# radio_module_V3_0.net
KiCad netlist of a schematic drawn in EAGLE
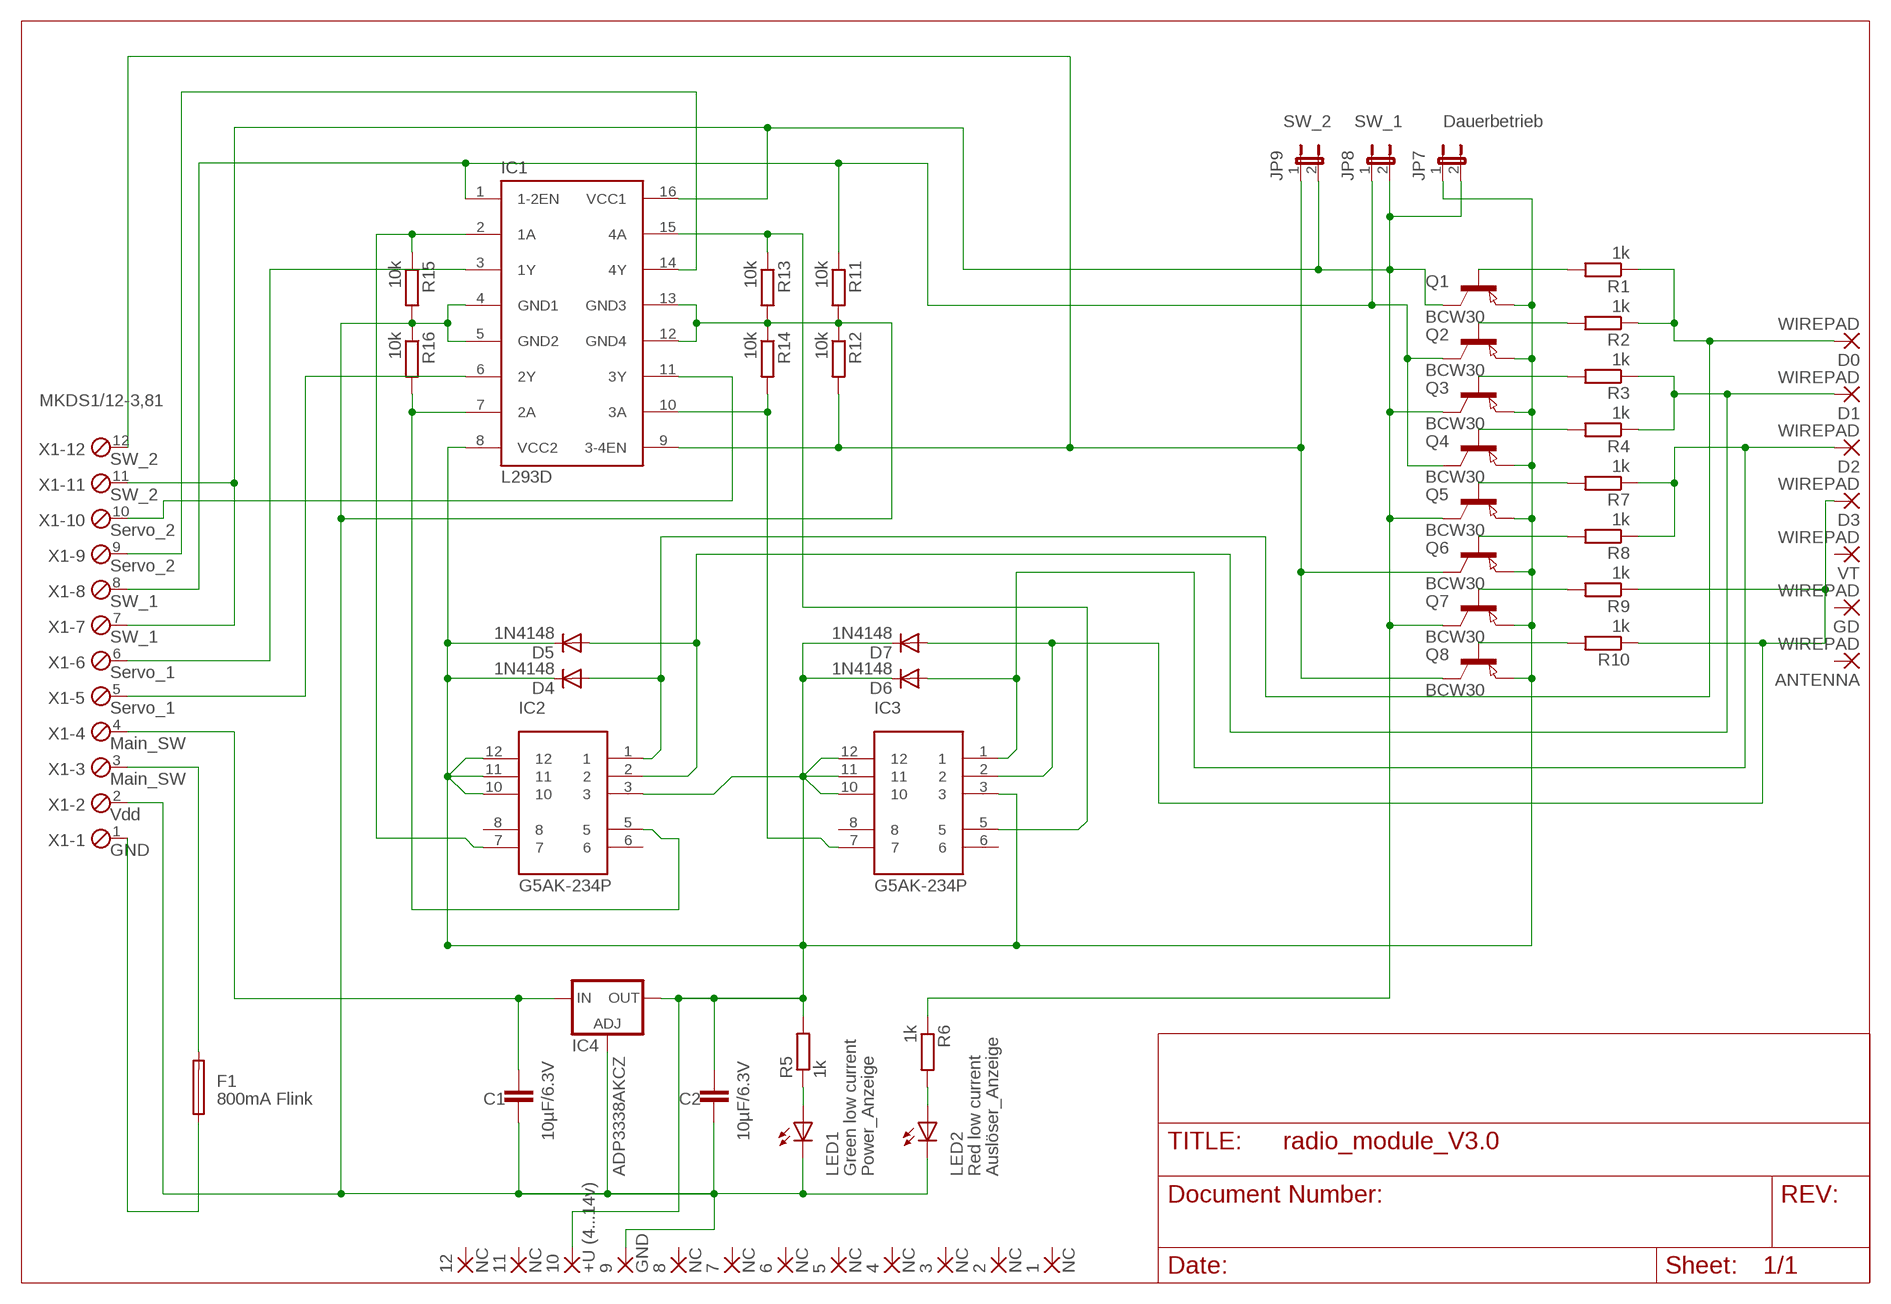
[diagram p0: schematic, sheet 1]

(export (version "E")
  (design (tool "Eeschema 10.0.6"))
  (components
    (comp (ref "1")
      (value "NC")
      (footprint "eagle-import:1,6_0,9")
      (libsource (lib "eagle-import") (part "1,6/0,9"))
    )
    (comp (ref "2")
      (value "NC")
      (footprint "eagle-import:1,6_0,9")
      (libsource (lib "eagle-import") (part "1,6/0,9"))
    )
    (comp (ref "3")
      (value "NC")
      (footprint "eagle-import:1,6_0,9")
      (libsource (lib "eagle-import") (part "1,6/0,9"))
    )
    (comp (ref "4")
      (value "NC")
      (footprint "eagle-import:1,6_0,9")
      (libsource (lib "eagle-import") (part "1,6/0,9"))
    )
    (comp (ref "5")
      (value "NC")
      (footprint "eagle-import:1,6_0,9")
      (libsource (lib "eagle-import") (part "1,6/0,9"))
    )
    (comp (ref "6")
      (value "NC")
      (footprint "eagle-import:1,6_0,9")
      (libsource (lib "eagle-import") (part "1,6/0,9"))
    )
    (comp (ref "7")
      (value "NC")
      (footprint "eagle-import:1,6_0,9")
      (libsource (lib "eagle-import") (part "1,6/0,9"))
    )
    (comp (ref "8")
      (value "NC")
      (footprint "eagle-import:1,6_0,9")
      (libsource (lib "eagle-import") (part "1,6/0,9"))
    )
    (comp (ref "9")
      (value "GND")
      (footprint "eagle-import:1,6_0,9")
      (libsource (lib "eagle-import") (part "1,6/0,9"))
    )
    (comp (ref "10")
      (value "+U (4...14v)")
      (footprint "eagle-import:1,6_0,9")
      (libsource (lib "eagle-import") (part "1,6/0,9"))
    )
    (comp (ref "11")
      (value "NC")
      (footprint "eagle-import:1,6_0,9")
      (libsource (lib "eagle-import") (part "1,6/0,9"))
    )
    (comp (ref "12")
      (value "NC")
      (footprint "eagle-import:1,6_0,9")
      (libsource (lib "eagle-import") (part "1,6/0,9"))
    )
    (comp (ref "ANTENNA")
      (value "WIREPAD")
      (footprint "eagle-import:1,6_0,9")
      (libsource (lib "eagle-import") (part "1,6/0,9"))
    )
    (comp (ref "C1")
      (value "10µF/6.3V")
      (footprint "eagle-import:C0805")
      (libsource (lib "eagle-import") (part "C-EUC0805"))
    )
    (comp (ref "C2")
      (value "10µF/6.3V")
      (footprint "eagle-import:C0805")
      (libsource (lib "eagle-import") (part "C-EUC0805"))
    )
    (comp (ref "D0")
      (value "WIREPAD")
      (footprint "eagle-import:1,6_0,9")
      (libsource (lib "eagle-import") (part "1,6/0,9"))
    )
    (comp (ref "D1")
      (value "WIREPAD")
      (footprint "eagle-import:1,6_0,9")
      (libsource (lib "eagle-import") (part "1,6/0,9"))
    )
    (comp (ref "D2")
      (value "WIREPAD")
      (footprint "eagle-import:1,6_0,9")
      (libsource (lib "eagle-import") (part "1,6/0,9"))
    )
    (comp (ref "D3")
      (value "WIREPAD")
      (footprint "eagle-import:1,6_0,9")
      (libsource (lib "eagle-import") (part "1,6/0,9"))
    )
    (comp (ref "D4")
      (value "1N4148")
      (footprint "eagle-import:DO35-7")
      (libsource (lib "eagle-import") (part "1N4148DO35-7"))
    )
    (comp (ref "D5")
      (value "1N4148")
      (footprint "eagle-import:DO35-7")
      (libsource (lib "eagle-import") (part "1N4148DO35-7"))
    )
    (comp (ref "D6")
      (value "1N4148")
      (footprint "eagle-import:DO35-7")
      (libsource (lib "eagle-import") (part "1N4148DO35-7"))
    )
    (comp (ref "D7")
      (value "1N4148")
      (footprint "eagle-import:DO35-7")
      (libsource (lib "eagle-import") (part "1N4148DO35-7"))
    )
    (comp (ref "F1")
      (value "800mA Flink")
      (footprint "eagle-import:19560")
      (libsource (lib "eagle-import") (part "FUSE19560"))
    )
    (comp (ref "GD")
      (value "WIREPAD")
      (footprint "eagle-import:1,6_0,9")
      (libsource (lib "eagle-import") (part "1,6/0,9"))
    )
    (comp (ref "IC1")
      (value "L293D")
      (footprint "eagle-import:DIL16")
      (libsource (lib "eagle-import") (part "L293D"))
    )
    (comp (ref "IC2")
      (value "G5AK-234P")
      (footprint "eagle-import:G5AK-234P")
      (libsource (lib "eagle-import") (part "G5AK-234P"))
    )
    (comp (ref "IC3")
      (value "G5AK-234P")
      (footprint "eagle-import:G5AK-234P")
      (libsource (lib "eagle-import") (part "G5AK-234P"))
    )
    (comp (ref "IC4")
      (value "ADP3338AKCZ")
      (footprint "eagle-import:SOT223")
      (libsource (lib "eagle-import") (part "LD117A?S12TR"))
    )
    (comp (ref "JP7")
      (value "Dauerbetrieb")
      (footprint "eagle-import:JP1")
      (libsource (lib "eagle-import") (part "JP1E"))
    )
    (comp (ref "JP8")
      (value "SW_1")
      (footprint "eagle-import:JP1")
      (libsource (lib "eagle-import") (part "JP1E"))
    )
    (comp (ref "JP9")
      (value "SW_2")
      (footprint "eagle-import:JP1")
      (libsource (lib "eagle-import") (part "JP1E"))
    )
    (comp (ref "LED1")
      (value "Green low current")
      (footprint "eagle-import:LED3MM")
      (libsource (lib "eagle-import") (part "LED3MM"))
    )
    (comp (ref "LED2")
      (value "Red low current")
      (footprint "eagle-import:LED3MM")
      (libsource (lib "eagle-import") (part "LED3MM"))
    )
    (comp (ref "Q1")
      (value "BCW30")
      (footprint "eagle-import:SOT23")
      (libsource (lib "eagle-import") (part "PNP-TRANSISTOR_SOT23"))
    )
    (comp (ref "Q2")
      (value "BCW30")
      (footprint "eagle-import:SOT23")
      (libsource (lib "eagle-import") (part "PNP-TRANSISTOR_SOT23"))
    )
    (comp (ref "Q3")
      (value "BCW30")
      (footprint "eagle-import:SOT23")
      (libsource (lib "eagle-import") (part "PNP-TRANSISTOR_SOT23"))
    )
    (comp (ref "Q4")
      (value "BCW30")
      (footprint "eagle-import:SOT23")
      (libsource (lib "eagle-import") (part "PNP-TRANSISTOR_SOT23"))
    )
    (comp (ref "Q5")
      (value "BCW30")
      (footprint "eagle-import:SOT23")
      (libsource (lib "eagle-import") (part "PNP-TRANSISTOR_SOT23"))
    )
    (comp (ref "Q6")
      (value "BCW30")
      (footprint "eagle-import:SOT23")
      (libsource (lib "eagle-import") (part "PNP-TRANSISTOR_SOT23"))
    )
    (comp (ref "Q7")
      (value "BCW30")
      (footprint "eagle-import:SOT23")
      (libsource (lib "eagle-import") (part "PNP-TRANSISTOR_SOT23"))
    )
    (comp (ref "Q8")
      (value "BCW30")
      (footprint "eagle-import:SOT23")
      (libsource (lib "eagle-import") (part "PNP-TRANSISTOR_SOT23"))
    )
    (comp (ref "R1")
      (value "1k")
      (footprint "eagle-import:R0402")
      (libsource (lib "eagle-import") (part "R-EU_R0402"))
    )
    (comp (ref "R2")
      (value "1k")
      (footprint "eagle-import:R0402")
      (libsource (lib "eagle-import") (part "R-EU_R0402"))
    )
    (comp (ref "R3")
      (value "1k")
      (footprint "eagle-import:R0402")
      (libsource (lib "eagle-import") (part "R-EU_R0402"))
    )
    (comp (ref "R4")
      (value "1k")
      (footprint "eagle-import:R0402")
      (libsource (lib "eagle-import") (part "R-EU_R0402"))
    )
    (comp (ref "R5")
      (value "1k")
      (footprint "eagle-import:R0402")
      (libsource (lib "eagle-import") (part "R-EU_R0402"))
    )
    (comp (ref "R6")
      (value "1k")
      (footprint "eagle-import:R0402")
      (libsource (lib "eagle-import") (part "R-EU_R0402"))
    )
    (comp (ref "R7")
      (value "1k")
      (footprint "eagle-import:R0402")
      (libsource (lib "eagle-import") (part "R-EU_R0402"))
    )
    (comp (ref "R8")
      (value "1k")
      (footprint "eagle-import:R0402")
      (libsource (lib "eagle-import") (part "R-EU_R0402"))
    )
    (comp (ref "R9")
      (value "1k")
      (footprint "eagle-import:R0402")
      (libsource (lib "eagle-import") (part "R-EU_R0402"))
    )
    (comp (ref "R10")
      (value "1k")
      (footprint "eagle-import:R0402")
      (libsource (lib "eagle-import") (part "R-EU_R0402"))
    )
    (comp (ref "R11")
      (value "10k")
      (footprint "eagle-import:R0402")
      (libsource (lib "eagle-import") (part "R-EU_R0402"))
    )
    (comp (ref "R12")
      (value "10k")
      (footprint "eagle-import:R0402")
      (libsource (lib "eagle-import") (part "R-EU_R0402"))
    )
    (comp (ref "R13")
      (value "10k")
      (footprint "eagle-import:R0402")
      (libsource (lib "eagle-import") (part "R-EU_R0402"))
    )
    (comp (ref "R14")
      (value "10k")
      (footprint "eagle-import:R0402")
      (libsource (lib "eagle-import") (part "R-EU_R0402"))
    )
    (comp (ref "R15")
      (value "10k")
      (footprint "eagle-import:R0402")
      (libsource (lib "eagle-import") (part "R-EU_R0402"))
    )
    (comp (ref "R16")
      (value "10k")
      (footprint "eagle-import:R0402")
      (libsource (lib "eagle-import") (part "R-EU_R0402"))
    )
    (comp (ref "VT")
      (value "WIREPAD")
      (footprint "eagle-import:1,6_0,9")
      (libsource (lib "eagle-import") (part "1,6/0,9"))
    )
    (comp (ref "X1")
      (value "MKDS1/12-3,81")
      (footprint "eagle-import:12POL381")
      (libsource (lib "eagle-import") (part "MKDS1/12-3,81"))
    )
  )
  (nets
    (net (code "1") (name "Net-(9-P)") (class "Default")
      (node (ref "9") (pin "1") (pinfunction "P_1") (pintype "passive"))
      (node (ref "C1") (pin "2") (pinfunction "2_2") (pintype "passive"))
      (node (ref "C2") (pin "2") (pinfunction "2_2") (pintype "passive"))
      (node (ref "IC1") (pin "12") (pinfunction "GND4_12") (pintype "power_in"))
      (node (ref "IC1") (pin "13") (pinfunction "GND3_13") (pintype "power_in"))
      (node (ref "IC1") (pin "4") (pinfunction "GND1_4") (pintype "power_in"))
      (node (ref "IC1") (pin "5") (pinfunction "GND2_5") (pintype "power_in"))
      (node (ref "IC4") (pin "1") (pinfunction "ADJ_1") (pintype "input"))
      (node (ref "LED1") (pin "K") (pinfunction "C_K") (pintype "passive"))
      (node (ref "LED2") (pin "K") (pinfunction "C_K") (pintype "passive"))
      (node (ref "R11") (pin "2") (pinfunction "2_2") (pintype "passive"))
      (node (ref "R12") (pin "1") (pinfunction "1_1") (pintype "passive"))
      (node (ref "R13") (pin "2") (pinfunction "2_2") (pintype "passive"))
      (node (ref "R14") (pin "1") (pinfunction "1_1") (pintype "passive"))
      (node (ref "R15") (pin "2") (pinfunction "2_2") (pintype "passive"))
      (node (ref "R16") (pin "1") (pinfunction "1_1") (pintype "passive"))
      (node (ref "X1") (pin "2") (pinfunction "1_2") (pintype "passive"))
    )
    (net (code "2") (name "Net-(10-P)") (class "Default")
      (node (ref "10") (pin "1") (pinfunction "P_1") (pintype "passive"))
      (node (ref "C2") (pin "1") (pinfunction "1_1") (pintype "passive"))
      (node (ref "D4") (pin "C") (pinfunction "C_C") (pintype "passive"))
      (node (ref "D5") (pin "C") (pinfunction "C_C") (pintype "passive"))
      (node (ref "D6") (pin "C") (pinfunction "C_C") (pintype "passive"))
      (node (ref "D7") (pin "C") (pinfunction "C_C") (pintype "passive"))
      (node (ref "IC1") (pin "8") (pinfunction "VCC2_8") (pintype "power_in"))
      (node (ref "IC2") (pin "10") (pinfunction "10_10") (pintype "bidirectional"))
      (node (ref "IC2") (pin "11") (pinfunction "11_11") (pintype "bidirectional"))
      (node (ref "IC2") (pin "12") (pinfunction "12_12") (pintype "bidirectional"))
      (node (ref "IC2") (pin "3") (pinfunction "3_3") (pintype "bidirectional"))
      (node (ref "IC3") (pin "10") (pinfunction "10_10") (pintype "bidirectional"))
      (node (ref "IC3") (pin "11") (pinfunction "11_11") (pintype "bidirectional"))
      (node (ref "IC3") (pin "12") (pinfunction "12_12") (pintype "bidirectional"))
      (node (ref "IC3") (pin "3") (pinfunction "3_3") (pintype "bidirectional"))
      (node (ref "IC4") (pin "4") (pinfunction "OUT_4") (pintype "passive"))
      (node (ref "JP7") (pin "1") (pinfunction "1_1") (pintype "passive"))
      (node (ref "Q1") (pin "2") (pinfunction "E_2") (pintype "passive"))
      (node (ref "Q2") (pin "2") (pinfunction "E_2") (pintype "passive"))
      (node (ref "Q3") (pin "2") (pinfunction "E_2") (pintype "passive"))
      (node (ref "Q4") (pin "2") (pinfunction "E_2") (pintype "passive"))
      (node (ref "Q5") (pin "2") (pinfunction "E_2") (pintype "passive"))
      (node (ref "Q6") (pin "2") (pinfunction "E_2") (pintype "passive"))
      (node (ref "Q7") (pin "2") (pinfunction "E_2") (pintype "passive"))
      (node (ref "Q8") (pin "2") (pinfunction "E_2") (pintype "passive"))
      (node (ref "R5") (pin "2") (pinfunction "2_2") (pintype "passive"))
    )
    (net (code "3") (name "Net-(D0-P)") (class "Default")
      (node (ref "D0") (pin "1") (pinfunction "P_1") (pintype "passive"))
      (node (ref "D4") (pin "A") (pinfunction "A_A") (pintype "passive"))
      (node (ref "IC2") (pin "1") (pinfunction "1_1") (pintype "bidirectional"))
      (node (ref "R1") (pin "1") (pinfunction "1_1") (pintype "passive"))
      (node (ref "R2") (pin "1") (pinfunction "1_1") (pintype "passive"))
    )
    (net (code "4") (name "Net-(D1-P)") (class "Default")
      (node (ref "D1") (pin "1") (pinfunction "P_1") (pintype "passive"))
      (node (ref "D5") (pin "A") (pinfunction "A_A") (pintype "passive"))
      (node (ref "IC2") (pin "2") (pinfunction "2_2") (pintype "bidirectional"))
      (node (ref "R3") (pin "1") (pinfunction "1_1") (pintype "passive"))
      (node (ref "R4") (pin "1") (pinfunction "1_1") (pintype "passive"))
    )
    (net (code "5") (name "Net-(D2-P)") (class "Default")
      (node (ref "D2") (pin "1") (pinfunction "P_1") (pintype "passive"))
      (node (ref "D6") (pin "A") (pinfunction "A_A") (pintype "passive"))
      (node (ref "IC3") (pin "1") (pinfunction "1_1") (pintype "bidirectional"))
      (node (ref "R7") (pin "1") (pinfunction "1_1") (pintype "passive"))
      (node (ref "R8") (pin "1") (pinfunction "1_1") (pintype "passive"))
    )
    (net (code "6") (name "Net-(D3-P)") (class "Default")
      (node (ref "D3") (pin "1") (pinfunction "P_1") (pintype "passive"))
      (node (ref "D7") (pin "A") (pinfunction "A_A") (pintype "passive"))
      (node (ref "IC3") (pin "2") (pinfunction "2_2") (pintype "bidirectional"))
      (node (ref "R10") (pin "1") (pinfunction "1_1") (pintype "passive"))
      (node (ref "R9") (pin "1") (pinfunction "1_1") (pintype "passive"))
    )
    (net (code "7") (name "Net-(F1-Pad1)") (class "Default")
      (node (ref "F1") (pin "1") (pinfunction "1_1") (pintype "passive"))
      (node (ref "X1") (pin "1") (pinfunction "1_1") (pintype "passive"))
    )
    (net (code "8") (name "Net-(IC1-1-2EN)") (class "Default")
      (node (ref "IC1") (pin "1") (pinfunction "1-2EN_1") (pintype "input"))
      (node (ref "JP8") (pin "1") (pinfunction "1_1") (pintype "passive"))
      (node (ref "Q2") (pin "3") (pinfunction "C_3") (pintype "passive"))
      (node (ref "Q4") (pin "3") (pinfunction "C_3") (pintype "passive"))
      (node (ref "R11") (pin "1") (pinfunction "1_1") (pintype "passive"))
      (node (ref "X1") (pin "8") (pinfunction "1_8") (pintype "passive"))
    )
    (net (code "9") (name "Net-(IC1-1A)") (class "Default")
      (node (ref "IC1") (pin "2") (pinfunction "1A_2") (pintype "input"))
      (node (ref "IC2") (pin "7") (pinfunction "7_7") (pintype "bidirectional"))
      (node (ref "R15") (pin "1") (pinfunction "1_1") (pintype "passive"))
    )
    (net (code "10") (name "Net-(IC1-1Y)") (class "Default")
      (node (ref "IC1") (pin "3") (pinfunction "1Y_3") (pintype "output"))
      (node (ref "X1") (pin "6") (pinfunction "1_6") (pintype "passive"))
    )
    (net (code "11") (name "Net-(IC1-2A)") (class "Default")
      (node (ref "IC1") (pin "7") (pinfunction "2A_7") (pintype "input"))
      (node (ref "IC2") (pin "5") (pinfunction "5_5") (pintype "bidirectional"))
      (node (ref "R16") (pin "2") (pinfunction "2_2") (pintype "passive"))
    )
    (net (code "12") (name "Net-(IC1-2Y)") (class "Default")
      (node (ref "IC1") (pin "6") (pinfunction "2Y_6") (pintype "output"))
      (node (ref "X1") (pin "5") (pinfunction "1_5") (pintype "passive"))
    )
    (net (code "13") (name "Net-(IC1-3-4EN)") (class "Default")
      (node (ref "IC1") (pin "9") (pinfunction "3-4EN_9") (pintype "input"))
      (node (ref "JP9") (pin "1") (pinfunction "1_1") (pintype "passive"))
      (node (ref "Q6") (pin "3") (pinfunction "C_3") (pintype "passive"))
      (node (ref "Q8") (pin "3") (pinfunction "C_3") (pintype "passive"))
      (node (ref "R12") (pin "2") (pinfunction "2_2") (pintype "passive"))
      (node (ref "X1") (pin "12") (pinfunction "1_12") (pintype "passive"))
    )
    (net (code "14") (name "Net-(IC1-3A)") (class "Default")
      (node (ref "IC1") (pin "10") (pinfunction "3A_10") (pintype "input"))
      (node (ref "IC3") (pin "7") (pinfunction "7_7") (pintype "bidirectional"))
      (node (ref "R14") (pin "2") (pinfunction "2_2") (pintype "passive"))
    )
    (net (code "15") (name "Net-(IC1-3Y)") (class "Default")
      (node (ref "IC1") (pin "11") (pinfunction "3Y_11") (pintype "output"))
      (node (ref "X1") (pin "10") (pinfunction "1_10") (pintype "passive"))
    )
    (net (code "16") (name "Net-(IC1-4A)") (class "Default")
      (node (ref "IC1") (pin "15") (pinfunction "4A_15") (pintype "input"))
      (node (ref "IC3") (pin "5") (pinfunction "5_5") (pintype "bidirectional"))
      (node (ref "R13") (pin "1") (pinfunction "1_1") (pintype "passive"))
    )
    (net (code "17") (name "Net-(IC1-4Y)") (class "Default")
      (node (ref "IC1") (pin "14") (pinfunction "4Y_14") (pintype "output"))
      (node (ref "X1") (pin "9") (pinfunction "1_9") (pintype "passive"))
    )
    (net (code "18") (name "Net-(IC1-VCC1)") (class "Default")
      (node (ref "IC1") (pin "16") (pinfunction "VCC1_16") (pintype "power_in"))
      (node (ref "JP7") (pin "2") (pinfunction "2_2") (pintype "passive"))
      (node (ref "JP8") (pin "2") (pinfunction "2_2") (pintype "passive"))
      (node (ref "JP9") (pin "2") (pinfunction "2_2") (pintype "passive"))
      (node (ref "Q1") (pin "3") (pinfunction "C_3") (pintype "passive"))
      (node (ref "Q3") (pin "3") (pinfunction "C_3") (pintype "passive"))
      (node (ref "Q5") (pin "3") (pinfunction "C_3") (pintype "passive"))
      (node (ref "Q7") (pin "3") (pinfunction "C_3") (pintype "passive"))
      (node (ref "R6") (pin "1") (pinfunction "1_1") (pintype "passive"))
      (node (ref "X1") (pin "11") (pinfunction "1_11") (pintype "passive"))
      (node (ref "X1") (pin "7") (pinfunction "1_7") (pintype "passive"))
    )
    (net (code "19") (name "Net-(IC4-IN)") (class "Default")
      (node (ref "C1") (pin "1") (pinfunction "1_1") (pintype "passive"))
      (node (ref "IC4") (pin "3") (pinfunction "IN_3") (pintype "input"))
      (node (ref "X1") (pin "4") (pinfunction "1_4") (pintype "passive"))
    )
    (net (code "20") (name "Net-(LED1-PadA)") (class "Default")
      (node (ref "LED1") (pin "A") (pinfunction "A_A") (pintype "passive"))
      (node (ref "R5") (pin "1") (pinfunction "1_1") (pintype "passive"))
    )
    (net (code "21") (name "Net-(LED2-PadA)") (class "Default")
      (node (ref "LED2") (pin "A") (pinfunction "A_A") (pintype "passive"))
      (node (ref "R6") (pin "2") (pinfunction "2_2") (pintype "passive"))
    )
    (net (code "22") (name "Net-(Q1-B)") (class "Default")
      (node (ref "Q1") (pin "1") (pinfunction "B_1") (pintype "passive"))
      (node (ref "R1") (pin "2") (pinfunction "2_2") (pintype "passive"))
    )
    (net (code "23") (name "Net-(Q2-B)") (class "Default")
      (node (ref "Q2") (pin "1") (pinfunction "B_1") (pintype "passive"))
      (node (ref "R2") (pin "2") (pinfunction "2_2") (pintype "passive"))
    )
    (net (code "24") (name "Net-(Q3-B)") (class "Default")
      (node (ref "Q3") (pin "1") (pinfunction "B_1") (pintype "passive"))
      (node (ref "R3") (pin "2") (pinfunction "2_2") (pintype "passive"))
    )
    (net (code "25") (name "Net-(Q4-B)") (class "Default")
      (node (ref "Q4") (pin "1") (pinfunction "B_1") (pintype "passive"))
      (node (ref "R4") (pin "2") (pinfunction "2_2") (pintype "passive"))
    )
    (net (code "26") (name "Net-(Q5-B)") (class "Default")
      (node (ref "Q5") (pin "1") (pinfunction "B_1") (pintype "passive"))
      (node (ref "R7") (pin "2") (pinfunction "2_2") (pintype "passive"))
    )
    (net (code "27") (name "Net-(Q6-B)") (class "Default")
      (node (ref "Q6") (pin "1") (pinfunction "B_1") (pintype "passive"))
      (node (ref "R8") (pin "2") (pinfunction "2_2") (pintype "passive"))
    )
    (net (code "28") (name "Net-(Q7-B)") (class "Default")
      (node (ref "Q7") (pin "1") (pinfunction "B_1") (pintype "passive"))
      (node (ref "R9") (pin "2") (pinfunction "2_2") (pintype "passive"))
    )
    (net (code "29") (name "Net-(Q8-B)") (class "Default")
      (node (ref "Q8") (pin "1") (pinfunction "B_1") (pintype "passive"))
      (node (ref "R10") (pin "2") (pinfunction "2_2") (pintype "passive"))
    )
    (net (code "30") (name "Net-(X1F-1)") (class "Default")
      (node (ref "F1") (pin "2") (pinfunction "2_2") (pintype "passive"))
      (node (ref "X1") (pin "3") (pinfunction "1_3") (pintype "passive"))
    )
    (net (code "31") (name "unconnected-(1-P-Pad1)") (class "Default")
      (node (ref "1") (pin "1") (pinfunction "P_1") (pintype "passive"))
    )
    (net (code "32") (name "unconnected-(2-P-Pad1)") (class "Default")
      (node (ref "2") (pin "1") (pinfunction "P_1") (pintype "passive"))
    )
    (net (code "33") (name "unconnected-(3-P-Pad1)") (class "Default")
      (node (ref "3") (pin "1") (pinfunction "P_1") (pintype "passive"))
    )
    (net (code "34") (name "unconnected-(4-P-Pad1)") (class "Default")
      (node (ref "4") (pin "1") (pinfunction "P_1") (pintype "passive"))
    )
    (net (code "35") (name "unconnected-(5-P-Pad1)") (class "Default")
      (node (ref "5") (pin "1") (pinfunction "P_1") (pintype "passive"))
    )
    (net (code "36") (name "unconnected-(6-P-Pad1)") (class "Default")
      (node (ref "6") (pin "1") (pinfunction "P_1") (pintype "passive"))
    )
    (net (code "37") (name "unconnected-(7-P-Pad1)") (class "Default")
      (node (ref "7") (pin "1") (pinfunction "P_1") (pintype "passive"))
    )
    (net (code "38") (name "unconnected-(8-P-Pad1)") (class "Default")
      (node (ref "8") (pin "1") (pinfunction "P_1") (pintype "passive"))
    )
    (net (code "39") (name "unconnected-(11-P-Pad1)") (class "Default")
      (node (ref "11") (pin "1") (pinfunction "P_1") (pintype "passive"))
    )
    (net (code "40") (name "unconnected-(12-P-Pad1)") (class "Default")
      (node (ref "12") (pin "1") (pinfunction "P_1") (pintype "passive"))
    )
    (net (code "41") (name "unconnected-(ANTENNA-P-Pad1)") (class "Default")
      (node (ref "ANTENNA") (pin "1") (pinfunction "P_1") (pintype "passive"))
    )
    (net (code "42") (name "unconnected-(GD-P-Pad1)") (class "Default")
      (node (ref "GD") (pin "1") (pinfunction "P_1") (pintype "passive"))
    )
    (net (code "43") (name "unconnected-(IC2-Pad6)") (class "Default")
      (node (ref "IC2") (pin "6") (pinfunction "6_6") (pintype "bidirectional"))
    )
    (net (code "44") (name "unconnected-(IC2-Pad8)") (class "Default")
      (node (ref "IC2") (pin "8") (pinfunction "8_8") (pintype "bidirectional"))
    )
    (net (code "45") (name "unconnected-(IC3-Pad6)") (class "Default")
      (node (ref "IC3") (pin "6") (pinfunction "6_6") (pintype "bidirectional"))
    )
    (net (code "46") (name "unconnected-(IC3-Pad8)") (class "Default")
      (node (ref "IC3") (pin "8") (pinfunction "8_8") (pintype "bidirectional"))
    )
    (net (code "47") (name "unconnected-(VT-P-Pad1)") (class "Default")
      (node (ref "VT") (pin "1") (pinfunction "P_1") (pintype "passive"))
    )
  )
)
